# opto.net
KiCad netlist of a schematic drawn in Altium Designer
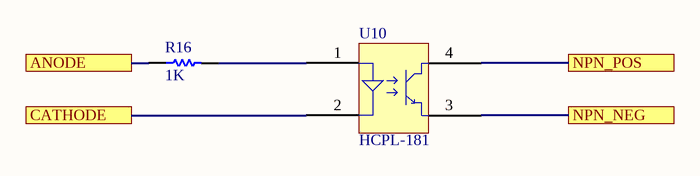
[diagram p0: opto.SchDoc]

(export (version "E")
  (design (tool "Eeschema 10.0.6"))
  (components
    (comp (ref "R16")
      (value "1K")
      (footprint "R0603")
      (description "Resistor,1K,0603,1%,1/10W")
      (fields
        (field (name "INTERNAL_PART_NUMBER") "MCD-00220")
        (field (name "MANUFACTURER_PART_NUMBER") "RC0603FR-0710KL")
        (field (name "PROVIDED_BY") "Subcon")
      )
      (libsource (lib "MCD_PARTS_database") (part "Resistor"))
    )
    (comp (ref "U10")
      (value "HCPL-181")
      (footprint "SOIC-4")
      (description "Optoacoplador")
      (libsource (lib "Project_PIER002.1.1") (part "HCPL-181"))
    )
  )
  (nets
    (net (code "1") (name "/ANODE") (class "Default")
      (node (ref "R16") (pin "1") (pinfunction "1_1") (pintype "passive"))
    )
    (net (code "2") (name "/CATHODE") (class "Default") (node (ref "U10") (pin "2") (pintype "passive")))
    (net (code "3") (name "/NPN_NEG") (class "Default") (node (ref "U10") (pin "3") (pintype "passive")))
    (net (code "4") (name "/NPN_POS") (class "Default") (node (ref "U10") (pin "4") (pintype "passive")))
    (net (code "5") (name "Net-(R16-Pad2)") (class "Default")
      (node (ref "R16") (pin "2") (pinfunction "2_2") (pintype "passive"))
      (node (ref "U10") (pin "1") (pintype "passive"))
    )
  )
)
